# lcdboard.net
KiCad netlist of a schematic drawn in EAGLE
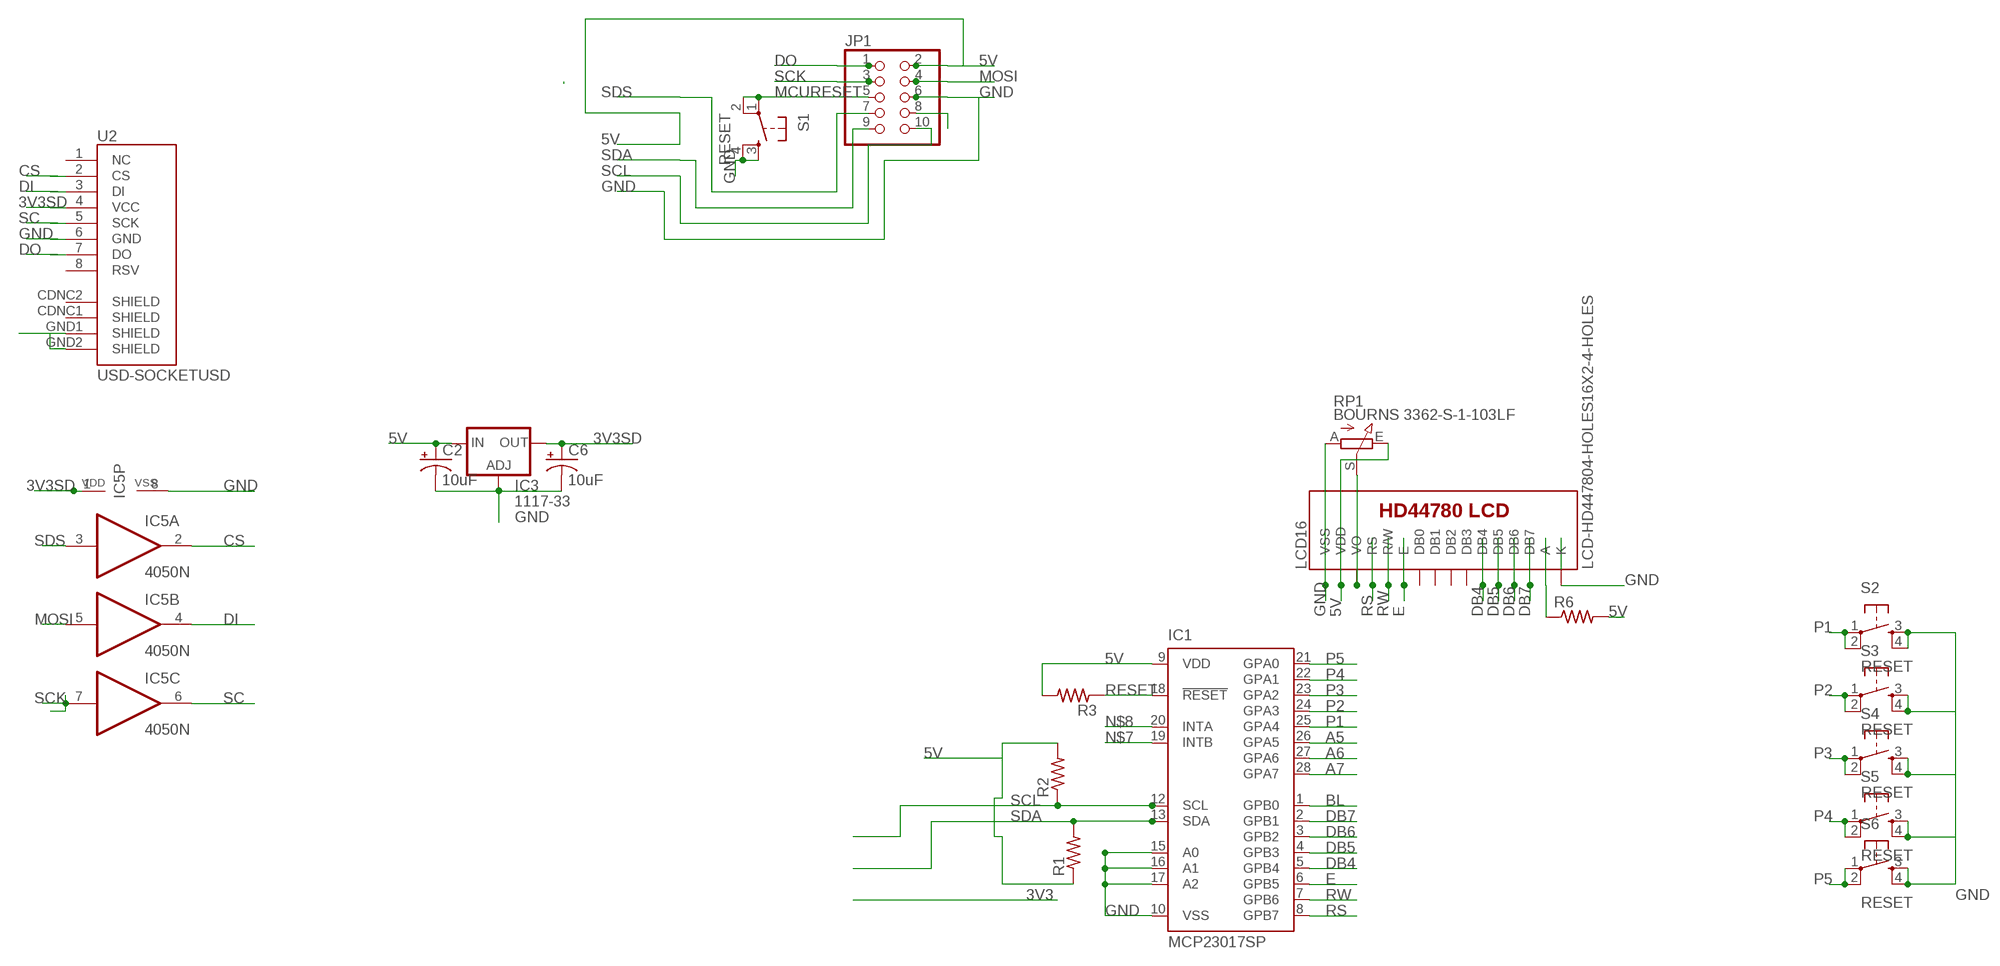
[diagram p0: schematic, sheet 1]

(export (version "E")
  (design (tool "Eeschema 10.0.6"))
  (components
    (comp (ref "C2")
      (value "10uF")
      (footprint "eagle-import:EIA3216")
      (libsource (lib "eagle-import") (part "CAP_POL1206"))
    )
    (comp (ref "C6")
      (value "10uF")
      (footprint "eagle-import:EIA3216")
      (libsource (lib "eagle-import") (part "CAP_POL1206"))
    )
    (comp (ref "IC1")
      (value "MCP23017SP")
      (footprint "eagle-import:DIL28-3")
      (libsource (lib "eagle-import") (part "MCP23017SP"))
    )
    (comp (ref "IC3")
      (value "1117-33")
      (footprint "eagle-import:SOT223")
      (libsource (lib "eagle-import") (part "LD117A?S33TR"))
    )
    (comp (ref "IC5")
      (value "4050N")
      (footprint "eagle-import:DIL16")
      (libsource (lib "eagle-import") (part "4050N"))
    )
    (comp (ref "JP1")
      (value "PINHD-2X5")
      (footprint "eagle-import:2X05")
      (libsource (lib "eagle-import") (part "PINHD-2X5"))
    )
    (comp (ref "LCD16")
      (value "LCD-HD447804-HOLES16X2-4-HOLES")
      (footprint "eagle-import:LCD-16X2-4HOLES")
      (libsource (lib "eagle-import") (part "LCD-HD4478016X2-4-HOLES4-HOLES"))
    )
    (comp (ref "R1")
      (value "R-US_0204/7")
      (footprint "eagle-import:0204_7")
      (libsource (lib "eagle-import") (part "R-US_0204/7"))
    )
    (comp (ref "R2")
      (value "R-US_0204/7")
      (footprint "eagle-import:0204_7")
      (libsource (lib "eagle-import") (part "R-US_0204/7"))
    )
    (comp (ref "R3")
      (value "R-US_0204/7")
      (footprint "eagle-import:0204_7")
      (libsource (lib "eagle-import") (part "R-US_0204/7"))
    )
    (comp (ref "R6")
      (value "R-US_0204/7")
      (footprint "eagle-import:0204_7")
      (libsource (lib "eagle-import") (part "R-US_0204/7"))
    )
    (comp (ref "RP1")
      (value "BOURNS 3362-S-1-103LF")
      (footprint "eagle-import:POT_B64W")
      (libsource (lib "eagle-import") (part "POTVERTICAL"))
    )
    (comp (ref "S1")
      (value "RESET")
      (footprint "eagle-import:TACTILE-PTH")
      (libsource (lib "eagle-import") (part "TAC_SWITCHPTH"))
    )
    (comp (ref "S2")
      (value "RESET")
      (footprint "eagle-import:TACTILE-PTH")
      (libsource (lib "eagle-import") (part "TAC_SWITCHPTH"))
    )
    (comp (ref "S3")
      (value "RESET")
      (footprint "eagle-import:TACTILE-PTH")
      (libsource (lib "eagle-import") (part "TAC_SWITCHPTH"))
    )
    (comp (ref "S4")
      (value "RESET")
      (footprint "eagle-import:TACTILE-PTH")
      (libsource (lib "eagle-import") (part "TAC_SWITCHPTH"))
    )
    (comp (ref "S5")
      (value "RESET")
      (footprint "eagle-import:TACTILE-PTH")
      (libsource (lib "eagle-import") (part "TAC_SWITCHPTH"))
    )
    (comp (ref "S6")
      (value "RESET")
      (footprint "eagle-import:TACTILE-PTH")
      (libsource (lib "eagle-import") (part "TAC_SWITCHPTH"))
    )
    (comp (ref "U2")
      (value "USD-SOCKETUSD")
      (footprint "eagle-import:USD-SOCKET-PP")
      (libsource (lib "eagle-import") (part "USD-SOCKETUSD"))
    )
  )
  (nets
    (net (code "2") (name "/3V3SD") (class "Default")
      (node (ref "C6") (pin "A") (pinfunction "+_A") (pintype "passive"))
      (node (ref "IC3") (pin "4") (pinfunction "OUT_4") (pintype "passive"))
      (node (ref "IC5") (pin "1") (pinfunction "VDD_1") (pintype "power_in"))
      (node (ref "U2") (pin "4") (pinfunction "VCC_4") (pintype "bidirectional"))
    )
    (net (code "3") (name "/5V") (class "Default")
      (node (ref "C2") (pin "A") (pinfunction "+_A") (pintype "passive"))
      (node (ref "IC1") (pin "9") (pinfunction "VDD_9") (pintype "power_in"))
      (node (ref "IC3") (pin "3") (pinfunction "IN_3") (pintype "input"))
      (node (ref "JP1") (pin "2") (pinfunction "2_2") (pintype "passive"))
      (node (ref "LCD16") (pin "2") (pinfunction "VDD_2") (pintype "power_in"))
      (node (ref "R1") (pin "1") (pinfunction "1_1") (pintype "passive"))
      (node (ref "R2") (pin "2") (pinfunction "2_2") (pintype "passive"))
      (node (ref "R3") (pin "2") (pinfunction "2_2") (pintype "passive"))
      (node (ref "R6") (pin "2") (pinfunction "2_2") (pintype "passive"))
      (node (ref "RP1") (pin "E") (pinfunction "E_E") (pintype "passive"))
    )
    (net (code "4") (name "/A5") (class "Default")
      (node (ref "IC1") (pin "26") (pinfunction "GPA5_26") (pintype "bidirectional"))
    )
    (net (code "5") (name "/A6") (class "Default")
      (node (ref "IC1") (pin "27") (pinfunction "GPA6_27") (pintype "bidirectional"))
    )
    (net (code "6") (name "/A7") (class "Default")
      (node (ref "IC1") (pin "28") (pinfunction "GPA7_28") (pintype "bidirectional"))
    )
    (net (code "7") (name "/BL") (class "Default")
      (node (ref "IC1") (pin "1") (pinfunction "GPB0_1") (pintype "bidirectional"))
    )
    (net (code "8") (name "/CS") (class "Default")
      (node (ref "IC5") (pin "2") (pinfunction "O_2") (pintype "output"))
      (node (ref "U2") (pin "2") (pinfunction "CS_2") (pintype "bidirectional"))
    )
    (net (code "9") (name "/DB4") (class "Default")
      (node (ref "IC1") (pin "5") (pinfunction "GPB4_5") (pintype "bidirectional"))
      (node (ref "LCD16") (pin "11") (pinfunction "DB4_11") (pintype "bidirectional"))
    )
    (net (code "10") (name "/DB5") (class "Default")
      (node (ref "IC1") (pin "4") (pinfunction "GPB3_4") (pintype "bidirectional"))
      (node (ref "LCD16") (pin "12") (pinfunction "DB5_12") (pintype "bidirectional"))
    )
    (net (code "11") (name "/DB6") (class "Default")
      (node (ref "IC1") (pin "3") (pinfunction "GPB2_3") (pintype "bidirectional"))
      (node (ref "LCD16") (pin "13") (pinfunction "DB6_13") (pintype "bidirectional"))
    )
    (net (code "12") (name "/DB7") (class "Default")
      (node (ref "IC1") (pin "2") (pinfunction "GPB1_2") (pintype "bidirectional"))
      (node (ref "LCD16") (pin "14") (pinfunction "DB7_14") (pintype "bidirectional"))
    )
    (net (code "13") (name "/DI") (class "Default")
      (node (ref "IC5") (pin "4") (pinfunction "O_4") (pintype "output"))
      (node (ref "U2") (pin "3") (pinfunction "DI_3") (pintype "bidirectional"))
    )
    (net (code "14") (name "/DO") (class "Default")
      (node (ref "JP1") (pin "1") (pinfunction "1_1") (pintype "passive"))
      (node (ref "U2") (pin "7") (pinfunction "DO_7") (pintype "bidirectional"))
    )
    (net (code "15") (name "/E") (class "Default")
      (node (ref "IC1") (pin "6") (pinfunction "GPB5_6") (pintype "bidirectional"))
      (node (ref "LCD16") (pin "6") (pinfunction "E_6") (pintype "input"))
    )
    (net (code "16") (name "/GND") (class "Default")
      (node (ref "C2") (pin "C") (pinfunction "-_C") (pintype "passive"))
      (node (ref "C6") (pin "C") (pinfunction "-_C") (pintype "passive"))
      (node (ref "IC1") (pin "10") (pinfunction "VSS_10") (pintype "power_in"))
      (node (ref "IC1") (pin "15") (pinfunction "A0_15") (pintype "input"))
      (node (ref "IC1") (pin "16") (pinfunction "A1_16") (pintype "input"))
      (node (ref "IC1") (pin "17") (pinfunction "A2_17") (pintype "input"))
      (node (ref "IC3") (pin "1") (pinfunction "ADJ_1") (pintype "input"))
      (node (ref "IC5") (pin "8") (pinfunction "VSS_8") (pintype "power_in"))
      (node (ref "JP1") (pin "6") (pinfunction "6_6") (pintype "passive"))
      (node (ref "LCD16") (pin "1") (pinfunction "VSS_1") (pintype "power_in"))
      (node (ref "LCD16") (pin "16") (pinfunction "K_16") (pintype "power_in"))
      (node (ref "RP1") (pin "A") (pinfunction "A_A") (pintype "passive"))
      (node (ref "S1") (pin "3") (pinfunction "3_3") (pintype "passive"))
      (node (ref "S1") (pin "4") (pinfunction "4_4") (pintype "passive"))
      (node (ref "S2") (pin "3") (pinfunction "3_3") (pintype "passive"))
      (node (ref "S2") (pin "4") (pinfunction "4_4") (pintype "passive"))
      (node (ref "S3") (pin "3") (pinfunction "3_3") (pintype "passive"))
      (node (ref "S3") (pin "4") (pinfunction "4_4") (pintype "passive"))
      (node (ref "S4") (pin "3") (pinfunction "3_3") (pintype "passive"))
      (node (ref "S4") (pin "4") (pinfunction "4_4") (pintype "passive"))
      (node (ref "S5") (pin "3") (pinfunction "3_3") (pintype "passive"))
      (node (ref "S5") (pin "4") (pinfunction "4_4") (pintype "passive"))
      (node (ref "S6") (pin "3") (pinfunction "3_3") (pintype "passive"))
      (node (ref "S6") (pin "4") (pinfunction "4_4") (pintype "passive"))
      (node (ref "U2") (pin "6") (pinfunction "GND_6") (pintype "bidirectional"))
      (node (ref "U2") (pin "GND1") (pinfunction "SHIELD_GND1") (pintype "bidirectional"))
      (node (ref "U2") (pin "GND2") (pinfunction "SHIELD_GND2") (pintype "bidirectional"))
    )
    (net (code "17") (name "/MCURESET") (class "Default")
      (node (ref "JP1") (pin "5") (pinfunction "5_5") (pintype "passive"))
      (node (ref "S1") (pin "1") (pinfunction "1_1") (pintype "passive"))
      (node (ref "S1") (pin "2") (pinfunction "2_2") (pintype "passive"))
    )
    (net (code "18") (name "/MOSI") (class "Default")
      (node (ref "IC5") (pin "5") (pinfunction "I_5") (pintype "input"))
      (node (ref "JP1") (pin "4") (pinfunction "4_4") (pintype "passive"))
    )
    (net (code "19") (name "/N$7") (class "Default")
      (node (ref "IC1") (pin "19") (pinfunction "INTB_19") (pintype "output"))
    )
    (net (code "20") (name "/N$8") (class "Default")
      (node (ref "IC1") (pin "20") (pinfunction "INTA_20") (pintype "output"))
    )
    (net (code "21") (name "/P1") (class "Default")
      (node (ref "IC1") (pin "25") (pinfunction "GPA4_25") (pintype "bidirectional"))
      (node (ref "S2") (pin "1") (pinfunction "1_1") (pintype "passive"))
      (node (ref "S2") (pin "2") (pinfunction "2_2") (pintype "passive"))
    )
    (net (code "22") (name "/P2") (class "Default")
      (node (ref "IC1") (pin "24") (pinfunction "GPA3_24") (pintype "bidirectional"))
      (node (ref "S3") (pin "1") (pinfunction "1_1") (pintype "passive"))
      (node (ref "S3") (pin "2") (pinfunction "2_2") (pintype "passive"))
    )
    (net (code "23") (name "/P3") (class "Default")
      (node (ref "IC1") (pin "23") (pinfunction "GPA2_23") (pintype "bidirectional"))
      (node (ref "S4") (pin "1") (pinfunction "1_1") (pintype "passive"))
      (node (ref "S4") (pin "2") (pinfunction "2_2") (pintype "passive"))
    )
    (net (code "24") (name "/P4") (class "Default")
      (node (ref "IC1") (pin "22") (pinfunction "GPA1_22") (pintype "bidirectional"))
      (node (ref "S5") (pin "1") (pinfunction "1_1") (pintype "passive"))
      (node (ref "S5") (pin "2") (pinfunction "2_2") (pintype "passive"))
    )
    (net (code "25") (name "/P5") (class "Default")
      (node (ref "IC1") (pin "21") (pinfunction "GPA0_21") (pintype "bidirectional"))
      (node (ref "S6") (pin "1") (pinfunction "1_1") (pintype "passive"))
      (node (ref "S6") (pin "2") (pinfunction "2_2") (pintype "passive"))
    )
    (net (code "26") (name "/RESET") (class "Default")
      (node (ref "IC1") (pin "18") (pinfunction "~{RESET}_18") (pintype "input"))
      (node (ref "R3") (pin "1") (pinfunction "1_1") (pintype "passive"))
    )
    (net (code "27") (name "/RS") (class "Default")
      (node (ref "IC1") (pin "8") (pinfunction "GPB7_8") (pintype "bidirectional"))
      (node (ref "LCD16") (pin "4") (pinfunction "RS_4") (pintype "input"))
    )
    (net (code "28") (name "/RW") (class "Default")
      (node (ref "IC1") (pin "7") (pinfunction "GPB6_7") (pintype "bidirectional"))
      (node (ref "LCD16") (pin "5") (pinfunction "R/W_5") (pintype "input"))
    )
    (net (code "29") (name "/SC") (class "Default")
      (node (ref "IC5") (pin "6") (pinfunction "O_6") (pintype "output"))
      (node (ref "U2") (pin "5") (pinfunction "SCK_5") (pintype "bidirectional"))
    )
    (net (code "30") (name "/SCK") (class "Default")
      (node (ref "IC5") (pin "7") (pinfunction "I_7") (pintype "input"))
      (node (ref "JP1") (pin "3") (pinfunction "3_3") (pintype "passive"))
    )
    (net (code "31") (name "/SCL") (class "Default")
      (node (ref "IC1") (pin "12") (pinfunction "SCL_12") (pintype "input"))
      (node (ref "JP1") (pin "10") (pinfunction "10_10") (pintype "passive"))
      (node (ref "R2") (pin "1") (pinfunction "1_1") (pintype "passive"))
    )
    (net (code "32") (name "/SDA") (class "Default")
      (node (ref "IC1") (pin "13") (pinfunction "SDA_13") (pintype "bidirectional"))
      (node (ref "JP1") (pin "9") (pinfunction "9_9") (pintype "passive"))
      (node (ref "R1") (pin "2") (pinfunction "2_2") (pintype "passive"))
    )
    (net (code "33") (name "/SDS") (class "Default")
      (node (ref "IC5") (pin "3") (pinfunction "I_3") (pintype "input"))
      (node (ref "JP1") (pin "7") (pinfunction "7_7") (pintype "passive"))
    )
    (net (code "34") (name "Net-(LCD16-A)") (class "Default")
      (node (ref "LCD16") (pin "15") (pinfunction "A_15") (pintype "power_in"))
      (node (ref "R6") (pin "1") (pinfunction "1_1") (pintype "passive"))
    )
    (net (code "35") (name "Net-(LCD16-VO)") (class "Default")
      (node (ref "LCD16") (pin "3") (pinfunction "VO_3") (pintype "bidirectional"))
      (node (ref "RP1") (pin "S") (pinfunction "S_S") (pintype "passive"))
    )
    (net (code "36") (name "unconnected-(JP1-Pad8)") (class "Default")
      (node (ref "JP1") (pin "8") (pinfunction "8_8") (pintype "passive"))
    )
    (net (code "37") (name "unconnected-(LCD16-DB0-Pad7)") (class "Default")
      (node (ref "LCD16") (pin "7") (pinfunction "DB0_7") (pintype "bidirectional"))
    )
    (net (code "38") (name "unconnected-(LCD16-DB1-Pad8)") (class "Default")
      (node (ref "LCD16") (pin "8") (pinfunction "DB1_8") (pintype "bidirectional"))
    )
    (net (code "39") (name "unconnected-(LCD16-DB2-Pad9)") (class "Default")
      (node (ref "LCD16") (pin "9") (pinfunction "DB2_9") (pintype "bidirectional"))
    )
    (net (code "40") (name "unconnected-(LCD16-DB3-Pad10)") (class "Default")
      (node (ref "LCD16") (pin "10") (pinfunction "DB3_10") (pintype "bidirectional"))
    )
    (net (code "41") (name "unconnected-(U2-NC-Pad1)") (class "Default")
      (node (ref "U2") (pin "1") (pinfunction "NC_1") (pintype "bidirectional"))
    )
    (net (code "42") (name "unconnected-(U2-RSV-Pad8)") (class "Default")
      (node (ref "U2") (pin "8") (pinfunction "RSV_8") (pintype "bidirectional"))
    )
    (net (code "43") (name "unconnected-(U2-SHIELD-PadCDNC1)") (class "Default")
      (node (ref "U2") (pin "CDNC1") (pinfunction "SHIELD_CDNC1") (pintype "bidirectional"))
    )
    (net (code "44") (name "unconnected-(U2-SHIELD-PadCDNC2)") (class "Default")
      (node (ref "U2") (pin "CDNC2") (pinfunction "SHIELD_CDNC2") (pintype "bidirectional"))
    )
  )
)
